# SCH_Taylor_2023-11-27.net
KiCad netlist of a schematic drawn in EasyEDA
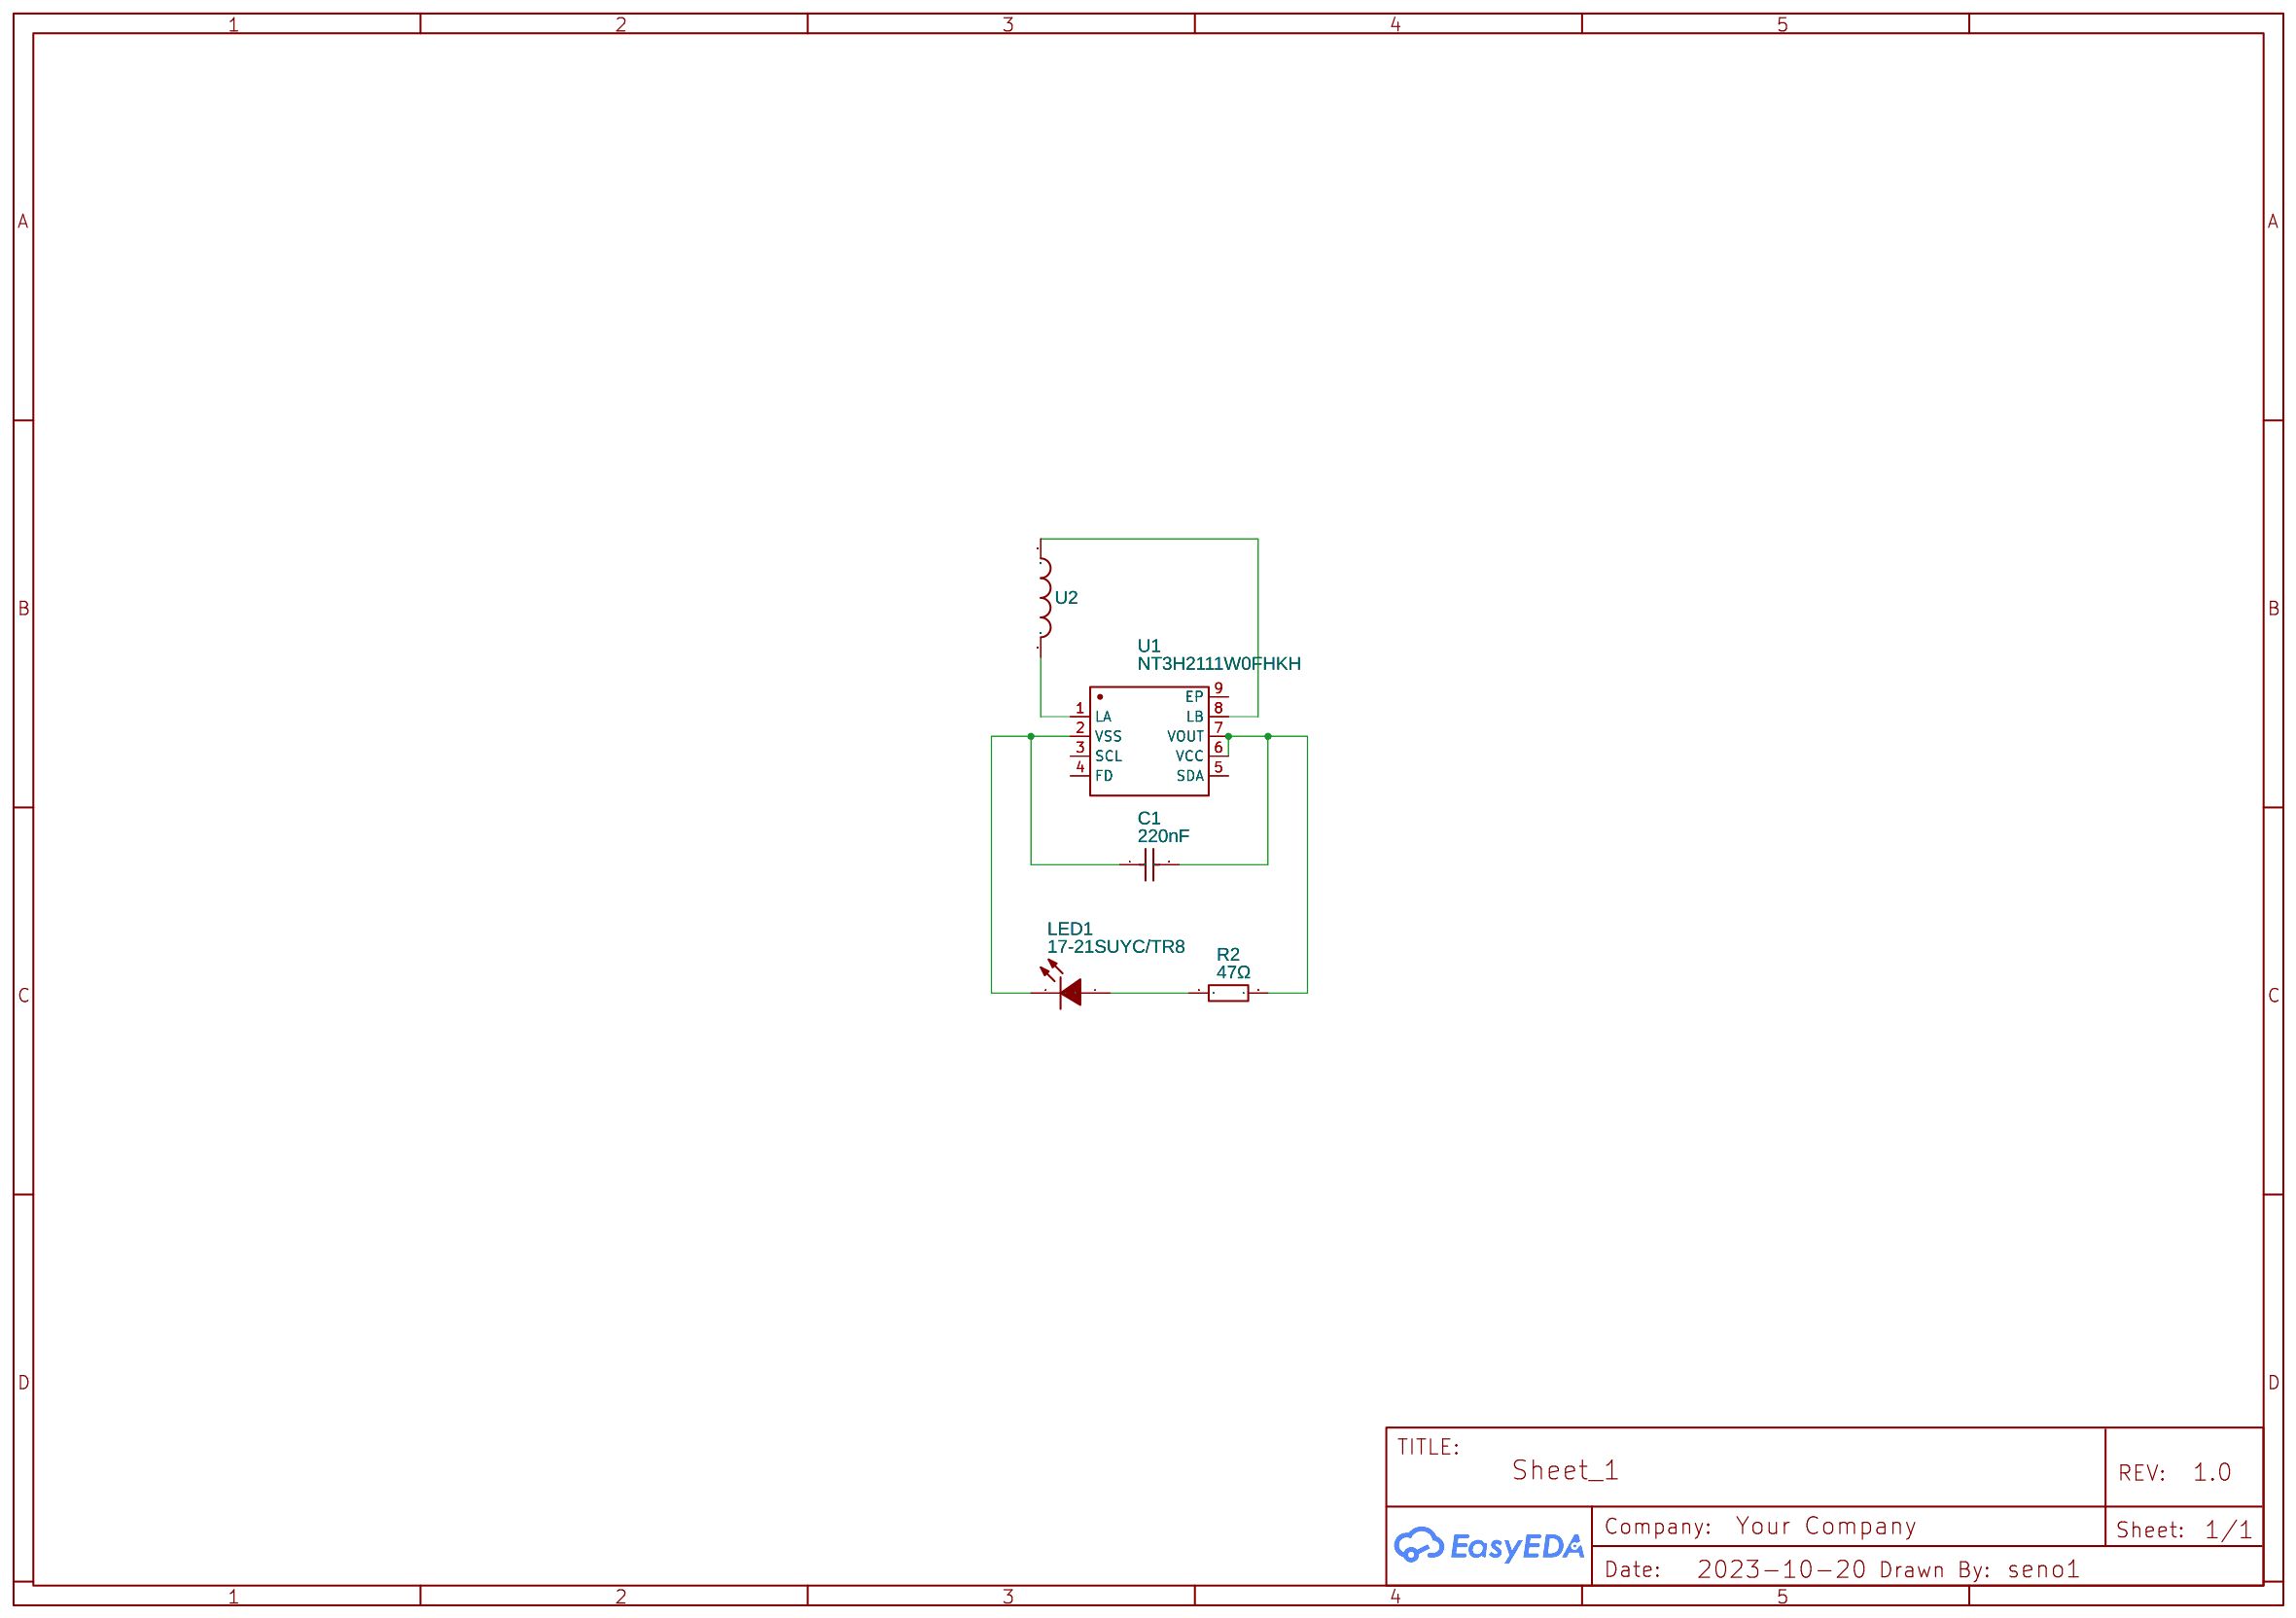
[diagram p0: schematic sheet]

(export (version "E")
  (design (tool "Eeschema 10.0.6"))
  (components
    (comp (ref "C1")
      (value "220nF")
      (fields
        (field (name "Manufacturer Part") "CL10B224KA8NNNC")
        (field (name "Manufacturer") "SAMSUNG(三星)")
      )
      (libsource (lib "") (part "CL10B224KA8NNNC"))
    )
    (comp (ref "LED1")
      (value "17-21SUYC/TR8")
      (fields (field (name "Manufacturer Part") "KT-0805黄灯") (field (name "Manufacturer") "KENTO"))
      (libsource (lib "") (part "17-21SUYC/TR8"))
    )
    (comp (ref "R2")
      (value "47Ω")
      (fields
        (field (name "Manufacturer Part") "0603WAF470JT5E")
        (field (name "Manufacturer") "UNI-ROYAL(厚声)")
      )
      (libsource (lib "") (part "0603WAF470JT5E"))
    )
    (comp (ref "U1")
      (value "NT3H2111W0FHKH")
      (fields (field (name "Manufacturer") "NXP(恩智浦)"))
      (libsource (lib "") (part "NT3H2111W0FHKH"))
    )
    (comp (ref "U2") (value "NO") (libsource (lib "") (part "25X48MM_NFC_ANTENNA")))
  )
  (nets
    (net (code "1") (name "Net-(LED1-+)") (class "Default")
      (node (ref "LED1") (pin "1") (pinfunction "+_1") (pintype "unspecified"))
      (node (ref "R2") (pin "1") (pinfunction "1_1") (pintype "input"))
    )
    (net (code "2") (name "Net-(LED1--)") (class "Default")
      (node (ref "C1") (pin "1") (pinfunction "1_1") (pintype "input"))
      (node (ref "LED1") (pin "2") (pinfunction "-_2") (pintype "unspecified"))
      (node (ref "U1") (pin "2") (pinfunction "VSS_2") (pintype "unspecified"))
    )
    (net (code "3") (name "Net-(U1-LA)") (class "Default")
      (node (ref "U1") (pin "1") (pinfunction "LA_1") (pintype "unspecified"))
      (node (ref "U2") (pin "P$2") (pinfunction "P$2_P$2") (pintype "bidirectional"))
    )
    (net (code "4") (name "Net-(U1-LB)") (class "Default")
      (node (ref "U1") (pin "8") (pinfunction "LB_8") (pintype "unspecified"))
      (node (ref "U2") (pin "P$1") (pinfunction "P$1_P$1") (pintype "bidirectional"))
    )
    (net (code "5") (name "Net-(U1-VCC)") (class "Default")
      (node (ref "C1") (pin "2") (pinfunction "2_2") (pintype "input"))
      (node (ref "R2") (pin "2") (pinfunction "2_2") (pintype "input"))
      (node (ref "U1") (pin "6") (pinfunction "VCC_6") (pintype "unspecified"))
      (node (ref "U1") (pin "7") (pinfunction "VOUT_7") (pintype "unspecified"))
    )
    (net (code "6") (name "unconnected-(U1-EP-Pad9)") (class "Default")
      (node (ref "U1") (pin "9") (pinfunction "EP_9") (pintype "unspecified"))
    )
    (net (code "7") (name "unconnected-(U1-FD-Pad4)") (class "Default")
      (node (ref "U1") (pin "4") (pinfunction "FD_4") (pintype "unspecified"))
    )
    (net (code "8") (name "unconnected-(U1-SCL-Pad3)") (class "Default")
      (node (ref "U1") (pin "3") (pinfunction "SCL_3") (pintype "unspecified"))
    )
    (net (code "9") (name "unconnected-(U1-SDA-Pad5)") (class "Default")
      (node (ref "U1") (pin "5") (pinfunction "SDA_5") (pintype "unspecified"))
    )
  )
)
